# ConnectorOut.net
KiCad netlist of a schematic drawn in Altium Designer
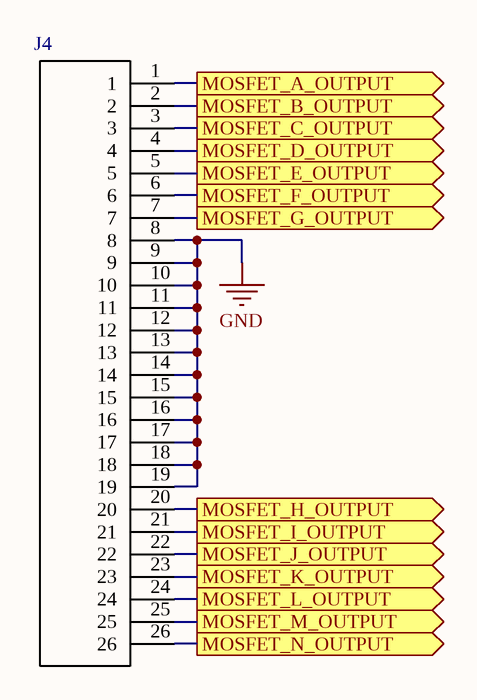
[diagram p0: ConnectorOut.SchDoc]

(export (version "E")
  (design (tool "Eeschema 10.0.6"))
  (components
    (comp (ref "J4")
      (value "6473418-1")
      (footprint "TE_6473418-1")
      (description "Conn Shrouded Header PIN 26 POS 3mm Solder ST Thru-Hole Automotive Tube")
      (fields (field (name "MF") "TE Connectivity") (field (name "DIGI-KEY_PART_NUMBER") "A121634-ND"))
      (libsource (lib "6473418-1") (part "6473418-1"))
    )
  )
  (nets
    (net (code "1") (name "/MOSFET_A_OUTPUT") (class "Default")
      (node (ref "J4") (pin "1") (pinfunction "1_1") (pintype "passive"))
    )
    (net (code "2") (name "/MOSFET_B_OUTPUT") (class "Default")
      (node (ref "J4") (pin "2") (pinfunction "2_2") (pintype "passive"))
    )
    (net (code "3") (name "/MOSFET_C_OUTPUT") (class "Default")
      (node (ref "J4") (pin "3") (pinfunction "3_3") (pintype "passive"))
    )
    (net (code "4") (name "/MOSFET_D_OUTPUT") (class "Default")
      (node (ref "J4") (pin "4") (pinfunction "4_4") (pintype "passive"))
    )
    (net (code "5") (name "/MOSFET_E_OUTPUT") (class "Default")
      (node (ref "J4") (pin "5") (pinfunction "5_5") (pintype "passive"))
    )
    (net (code "6") (name "/MOSFET_F_OUTPUT") (class "Default")
      (node (ref "J4") (pin "6") (pinfunction "6_6") (pintype "passive"))
    )
    (net (code "7") (name "/MOSFET_G_OUTPUT") (class "Default")
      (node (ref "J4") (pin "7") (pinfunction "7_7") (pintype "passive"))
    )
    (net (code "8") (name "/MOSFET_H_OUTPUT") (class "Default")
      (node (ref "J4") (pin "20") (pinfunction "20_20") (pintype "passive"))
    )
    (net (code "9") (name "/MOSFET_I_OUTPUT") (class "Default")
      (node (ref "J4") (pin "21") (pinfunction "21_21") (pintype "passive"))
    )
    (net (code "10") (name "/MOSFET_J_OUTPUT") (class "Default")
      (node (ref "J4") (pin "22") (pinfunction "22_22") (pintype "passive"))
    )
    (net (code "11") (name "/MOSFET_K_OUTPUT") (class "Default")
      (node (ref "J4") (pin "23") (pinfunction "23_23") (pintype "passive"))
    )
    (net (code "12") (name "/MOSFET_L_OUTPUT") (class "Default")
      (node (ref "J4") (pin "24") (pinfunction "24_24") (pintype "passive"))
    )
    (net (code "13") (name "/MOSFET_M_OUTPUT") (class "Default")
      (node (ref "J4") (pin "25") (pinfunction "25_25") (pintype "passive"))
    )
    (net (code "14") (name "/MOSFET_N_OUTPUT") (class "Default")
      (node (ref "J4") (pin "26") (pinfunction "26_26") (pintype "passive"))
    )
    (net (code "15") (name "GND") (class "Default")
      (node (ref "J4") (pin "10") (pinfunction "10_10") (pintype "passive"))
      (node (ref "J4") (pin "11") (pinfunction "11_11") (pintype "passive"))
      (node (ref "J4") (pin "12") (pinfunction "12_12") (pintype "passive"))
      (node (ref "J4") (pin "13") (pinfunction "13_13") (pintype "passive"))
      (node (ref "J4") (pin "14") (pinfunction "14_14") (pintype "passive"))
      (node (ref "J4") (pin "15") (pinfunction "15_15") (pintype "passive"))
      (node (ref "J4") (pin "16") (pinfunction "16_16") (pintype "passive"))
      (node (ref "J4") (pin "17") (pinfunction "17_17") (pintype "passive"))
      (node (ref "J4") (pin "18") (pinfunction "18_18") (pintype "passive"))
      (node (ref "J4") (pin "19") (pinfunction "19_19") (pintype "passive"))
      (node (ref "J4") (pin "8") (pinfunction "8_8") (pintype "passive"))
      (node (ref "J4") (pin "9") (pinfunction "9_9") (pintype "passive"))
    )
  )
)
